# motoko_azure_dragon.net
KiCad netlist of a schematic drawn in EAGLE
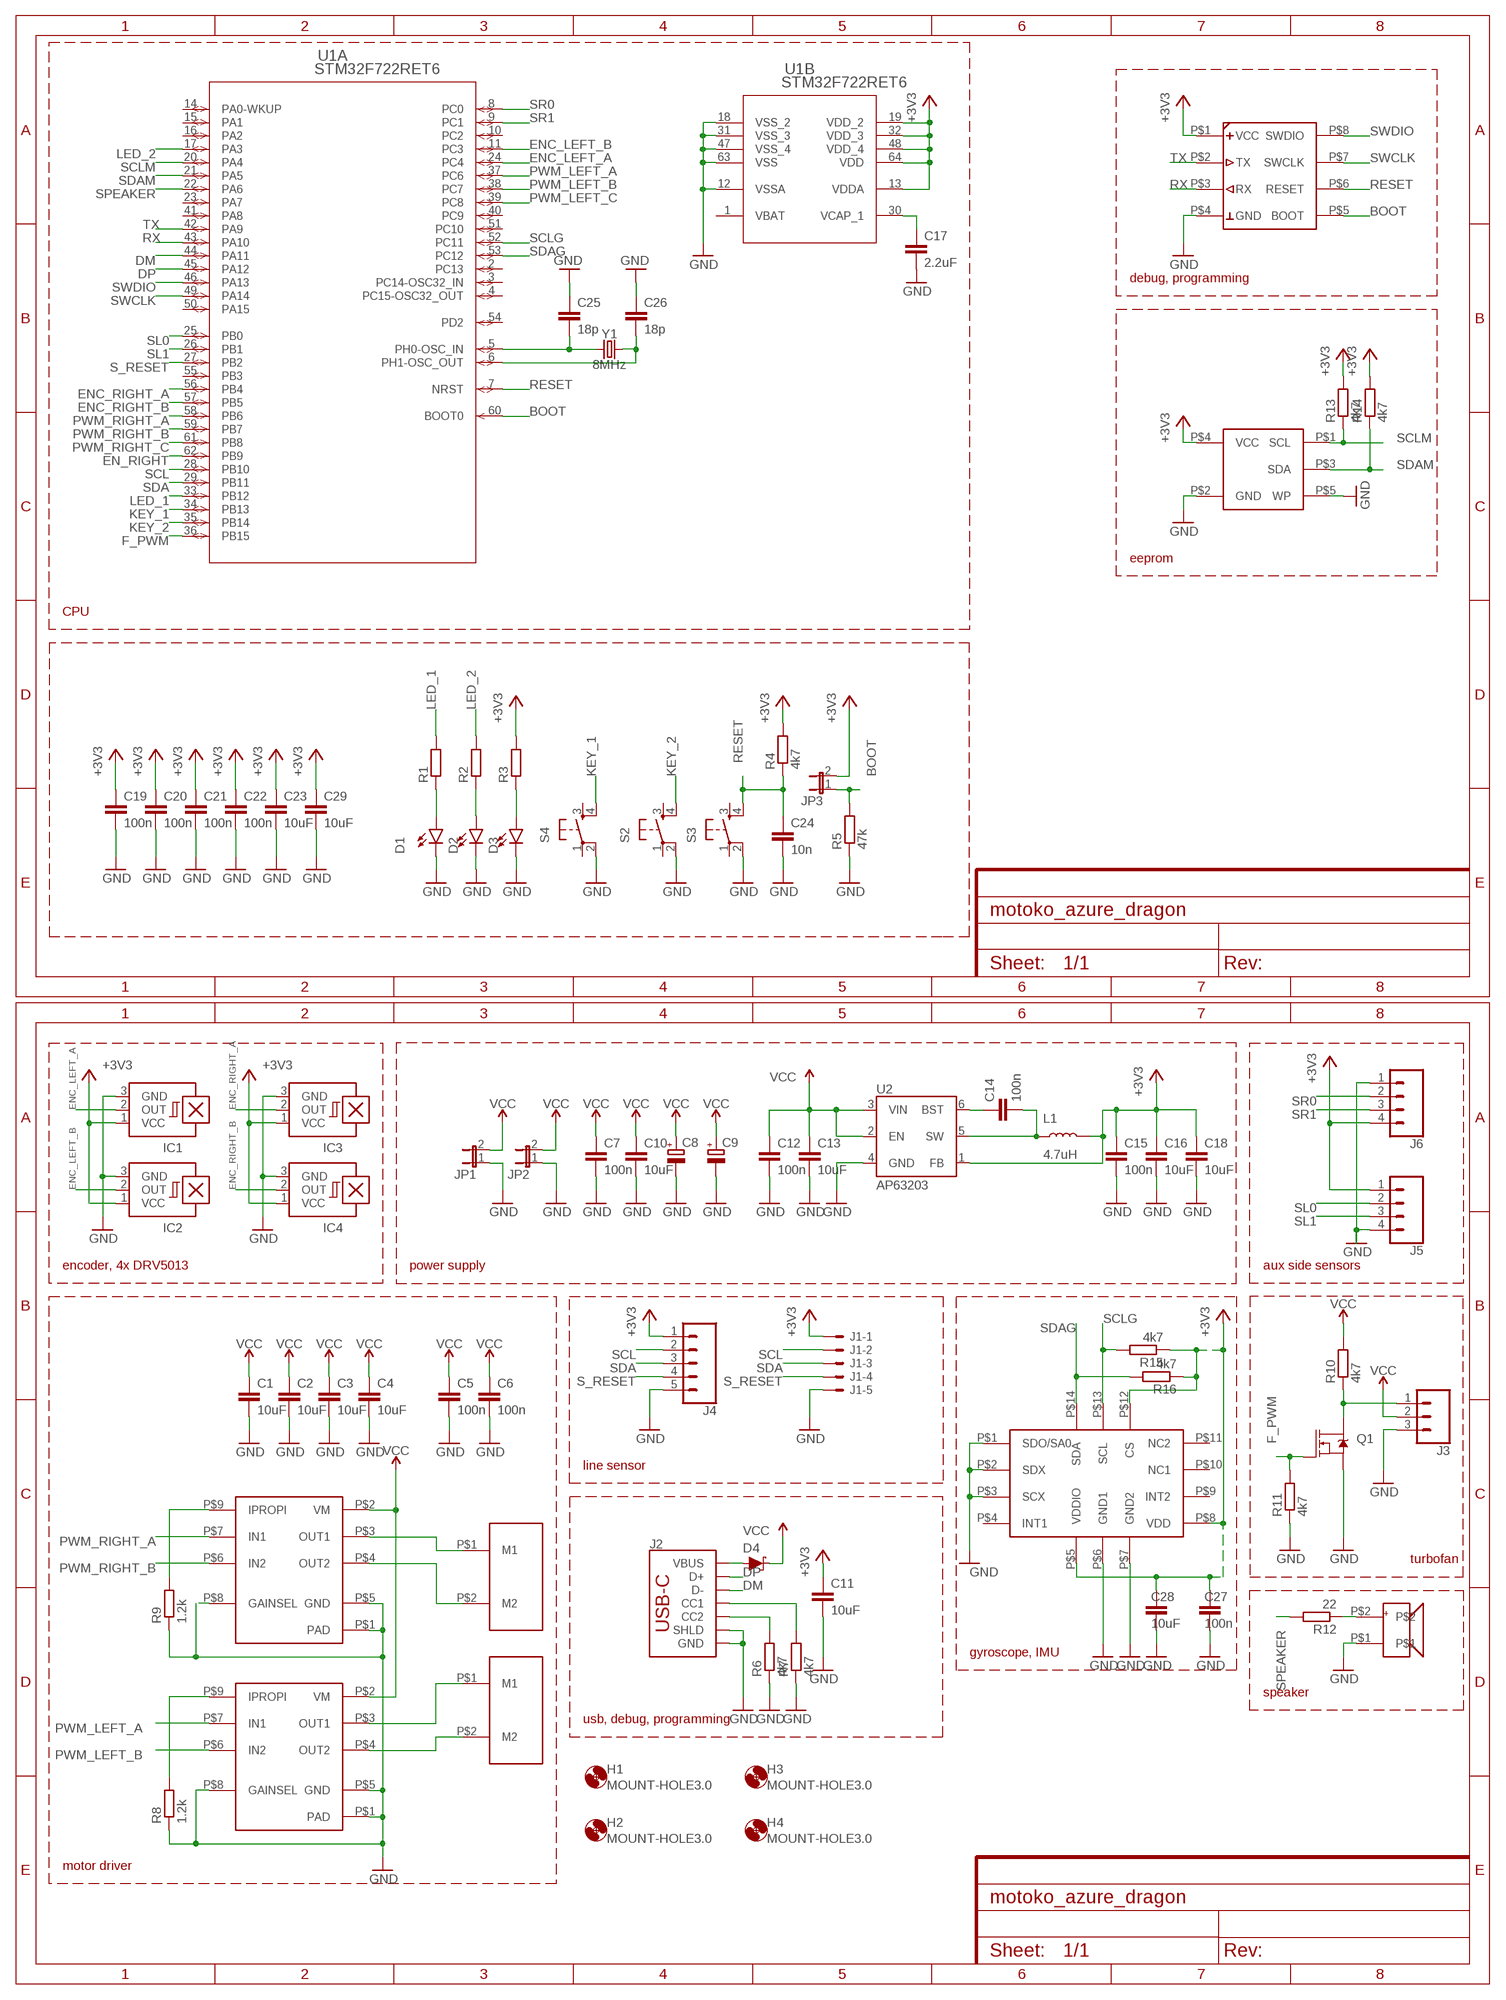
[diagram p0: schematic, sheet 1]

(export (version "E")
  (design (tool "Eeschema 10.0.6"))
  (components
    (comp (ref "C1")
      (value "10uF")
      (footprint "eagle-import:C0805")
      (libsource (lib "eagle-import") (part "C-EUC0805"))
    )
    (comp (ref "C2")
      (value "10uF")
      (footprint "eagle-import:C0805")
      (libsource (lib "eagle-import") (part "C-EUC0805"))
    )
    (comp (ref "C3")
      (value "10uF")
      (footprint "eagle-import:C0805")
      (libsource (lib "eagle-import") (part "C-EUC0805"))
    )
    (comp (ref "C4")
      (value "10uF")
      (footprint "eagle-import:C0805")
      (libsource (lib "eagle-import") (part "C-EUC0805"))
    )
    (comp (ref "C5")
      (value "100n")
      (footprint "eagle-import:C0805")
      (libsource (lib "eagle-import") (part "C-EUC0805"))
    )
    (comp (ref "C6")
      (value "100n")
      (footprint "eagle-import:C0805")
      (libsource (lib "eagle-import") (part "C-EUC0805"))
    )
    (comp (ref "C7")
      (value "100n")
      (footprint "eagle-import:C0805")
      (libsource (lib "eagle-import") (part "C-EUC0805"))
    )
    (comp (ref "C8")
      (value "CPOL-EUB/3528-21W")
      (footprint "eagle-import:B_3528-21W")
      (libsource (lib "eagle-import") (part "CPOL-EUB/3528-21W"))
    )
    (comp (ref "C9")
      (value "CPOL-EUB/3528-21W")
      (footprint "eagle-import:B_3528-21W")
      (libsource (lib "eagle-import") (part "CPOL-EUB/3528-21W"))
    )
    (comp (ref "C10")
      (value "10uF")
      (footprint "eagle-import:C0805")
      (libsource (lib "eagle-import") (part "C-EUC0805"))
    )
    (comp (ref "C11")
      (value "10uF")
      (footprint "eagle-import:C0805")
      (libsource (lib "eagle-import") (part "C-EUC0805"))
    )
    (comp (ref "C12")
      (value "100n")
      (footprint "eagle-import:C0805")
      (libsource (lib "eagle-import") (part "C-EUC0805"))
    )
    (comp (ref "C13")
      (value "10uF")
      (footprint "eagle-import:C0805")
      (libsource (lib "eagle-import") (part "C-EUC0805"))
    )
    (comp (ref "C14")
      (value "100n")
      (footprint "eagle-import:C0805")
      (libsource (lib "eagle-import") (part "C-EUC0805"))
    )
    (comp (ref "C15")
      (value "100n")
      (footprint "eagle-import:C0805")
      (libsource (lib "eagle-import") (part "C-EUC0805"))
    )
    (comp (ref "C16")
      (value "10uF")
      (footprint "eagle-import:C0805")
      (libsource (lib "eagle-import") (part "C-EUC0805"))
    )
    (comp (ref "C17")
      (value "2.2uF")
      (footprint "eagle-import:C0805")
      (libsource (lib "eagle-import") (part "C-EUC0805"))
    )
    (comp (ref "C18")
      (value "10uF")
      (footprint "eagle-import:C0805")
      (libsource (lib "eagle-import") (part "C-EUC0805"))
    )
    (comp (ref "C19")
      (value "100n")
      (footprint "eagle-import:C0805")
      (libsource (lib "eagle-import") (part "C-EUC0805"))
    )
    (comp (ref "C20")
      (value "100n")
      (footprint "eagle-import:C0805")
      (libsource (lib "eagle-import") (part "C-EUC0805"))
    )
    (comp (ref "C21")
      (value "100n")
      (footprint "eagle-import:C0805")
      (libsource (lib "eagle-import") (part "C-EUC0805"))
    )
    (comp (ref "C22")
      (value "100n")
      (footprint "eagle-import:C0805")
      (libsource (lib "eagle-import") (part "C-EUC0805"))
    )
    (comp (ref "C23")
      (value "10uF")
      (footprint "eagle-import:C0805")
      (libsource (lib "eagle-import") (part "C-EUC0805"))
    )
    (comp (ref "C24")
      (value "10n")
      (footprint "eagle-import:C0805")
      (libsource (lib "eagle-import") (part "C-EUC0805"))
    )
    (comp (ref "C25")
      (value "18p")
      (footprint "eagle-import:C0805")
      (libsource (lib "eagle-import") (part "C-EUC0805"))
    )
    (comp (ref "C26")
      (value "18p")
      (footprint "eagle-import:C0805")
      (libsource (lib "eagle-import") (part "C-EUC0805"))
    )
    (comp (ref "C27")
      (value "100n")
      (footprint "eagle-import:C0805")
      (libsource (lib "eagle-import") (part "C-EUC0805"))
    )
    (comp (ref "C28")
      (value "10uF")
      (footprint "eagle-import:C0805")
      (libsource (lib "eagle-import") (part "C-EUC0805"))
    )
    (comp (ref "C29")
      (value "10uF")
      (footprint "eagle-import:C0805")
      (libsource (lib "eagle-import") (part "C-EUC0805"))
    )
    (comp (ref "D1")
      (value "LED1206")
      (footprint "eagle-import:LED-1206")
      (libsource (lib "eagle-import") (part "LED1206"))
    )
    (comp (ref "D2")
      (value "LED1206")
      (footprint "eagle-import:LED-1206")
      (libsource (lib "eagle-import") (part "LED1206"))
    )
    (comp (ref "D3")
      (value "LED1206")
      (footprint "eagle-import:LED-1206")
      (libsource (lib "eagle-import") (part "LED1206"))
    )
    (comp (ref "D4")
      (value "3A/10V/280mV")
      (footprint "eagle-import:SOD-323")
      (libsource (lib "eagle-import") (part "DIODE-SCHOTTKY-BAT60A"))
    )
    (comp (ref "H1")
      (value "MOUNT-HOLE3.0")
      (footprint "eagle-import:3,0")
      (libsource (lib "eagle-import") (part "MOUNT-HOLE3.0"))
    )
    (comp (ref "H2")
      (value "MOUNT-HOLE3.0")
      (footprint "eagle-import:3,0")
      (libsource (lib "eagle-import") (part "MOUNT-HOLE3.0"))
    )
    (comp (ref "H3")
      (value "MOUNT-HOLE3.0")
      (footprint "eagle-import:3,0")
      (libsource (lib "eagle-import") (part "MOUNT-HOLE3.0"))
    )
    (comp (ref "H4")
      (value "MOUNT-HOLE3.0")
      (footprint "eagle-import:3,0")
      (libsource (lib "eagle-import") (part "MOUNT-HOLE3.0"))
    )
    (comp (ref "IC1")
      (value "A1202LH")
      (footprint "eagle-import:SOT23-W")
      (libsource (lib "eagle-import") (part "A12?LH02"))
    )
    (comp (ref "IC2")
      (value "A1202LH")
      (footprint "eagle-import:SOT23-W")
      (libsource (lib "eagle-import") (part "A12?LH02"))
    )
    (comp (ref "IC3")
      (value "A1202LH")
      (footprint "eagle-import:SOT23-W")
      (libsource (lib "eagle-import") (part "A12?LH02"))
    )
    (comp (ref "IC4")
      (value "A1202LH")
      (footprint "eagle-import:SOT23-W")
      (libsource (lib "eagle-import") (part "A12?LH02"))
    )
    (comp (ref "J1")
      (value "XF2L-0535-1")
      (footprint "eagle-import:XF2L-0535-1")
      (fields (field (name "MPN") "XF2L-0535-1A"))
      (libsource (lib "eagle-import") (part "XF2-05?35-1L"))
    )
    (comp (ref "J2")
      (value "USB_C_2-LAYER_PADS")
      (footprint "eagle-import:USB-C-16P-2LAYER-PADS")
      (libsource (lib "eagle-import") (part "USB_C_2-LAYER_PADS"))
    )
    (comp (ref "J3")
      (value "CONN_03LONGPADS")
      (footprint "eagle-import:1X03_LONGPADS")
      (libsource (lib "eagle-import") (part "CONN_03LONGPADS"))
    )
    (comp (ref "J4")
      (value "CONN_051.27MM")
      (footprint "eagle-import:1X05_1.27MM")
      (libsource (lib "eagle-import") (part "CONN_051.27MM"))
    )
    (comp (ref "J5")
      (value "1X04_SMD_STRAIGHT_COMBO")
      (footprint "eagle-import:1X04_SMD_VERTICAL_COMBO")
      (libsource (lib "eagle-import") (part "CONN_04SMD_STRAIGHT_COMBO"))
    )
    (comp (ref "J6")
      (value "1X04_SMD_STRAIGHT_COMBO")
      (footprint "eagle-import:1X04_SMD_VERTICAL_COMBO")
      (libsource (lib "eagle-import") (part "CONN_04SMD_STRAIGHT_COMBO"))
    )
    (comp (ref "JP1")
      (value "JP1E")
      (footprint "eagle-import:JP1")
      (libsource (lib "eagle-import") (part "JP1E"))
    )
    (comp (ref "JP2")
      (value "JP1E")
      (footprint "eagle-import:JP1")
      (libsource (lib "eagle-import") (part "JP1E"))
    )
    (comp (ref "JP3")
      (value "JP1E")
      (footprint "eagle-import:JP1")
      (libsource (lib "eagle-import") (part "JP1E"))
    )
    (comp (ref "L1")
      (value "4.7uH")
      (footprint "eagle-import:CR54")
      (libsource (lib "eagle-import") (part "INDUCTOR-CR54-3.3UH"))
    )
    (comp (ref "Q1")
      (value "5.8A/30V/35mΩ")
      (footprint "eagle-import:SOT23-3")
      (libsource (lib "eagle-import") (part "MOSFET-NCH-AO3404A"))
    )
    (comp (ref "R1")
      (value "R-EU_M0805")
      (footprint "eagle-import:M0805")
      (libsource (lib "eagle-import") (part "R-EU_M0805"))
    )
    (comp (ref "R2")
      (value "R-EU_M0805")
      (footprint "eagle-import:M0805")
      (libsource (lib "eagle-import") (part "R-EU_M0805"))
    )
    (comp (ref "R3")
      (value "R-EU_M0805")
      (footprint "eagle-import:M0805")
      (libsource (lib "eagle-import") (part "R-EU_M0805"))
    )
    (comp (ref "R4")
      (value "4k7")
      (footprint "eagle-import:M0805")
      (libsource (lib "eagle-import") (part "R-EU_M0805"))
    )
    (comp (ref "R5")
      (value "47k")
      (footprint "eagle-import:M0805")
      (libsource (lib "eagle-import") (part "R-EU_M0805"))
    )
    (comp (ref "R6")
      (value "4k7")
      (footprint "eagle-import:M0805")
      (libsource (lib "eagle-import") (part "R-EU_M0805"))
    )
    (comp (ref "R7")
      (value "4k7")
      (footprint "eagle-import:M0805")
      (libsource (lib "eagle-import") (part "R-EU_M0805"))
    )
    (comp (ref "R8")
      (value "1.2k")
      (footprint "eagle-import:M0805")
      (libsource (lib "eagle-import") (part "R-EU_M0805"))
    )
    (comp (ref "R9")
      (value "1.2k")
      (footprint "eagle-import:M0805")
      (libsource (lib "eagle-import") (part "R-EU_M0805"))
    )
    (comp (ref "R10")
      (value "4k7")
      (footprint "eagle-import:M0805")
      (libsource (lib "eagle-import") (part "R-EU_M0805"))
    )
    (comp (ref "R11")
      (value "4k7")
      (footprint "eagle-import:M0805")
      (libsource (lib "eagle-import") (part "R-EU_M0805"))
    )
    (comp (ref "R12")
      (value "22")
      (footprint "eagle-import:M0805")
      (libsource (lib "eagle-import") (part "R-EU_M0805"))
    )
    (comp (ref "R13")
      (value "4k7")
      (footprint "eagle-import:M0805")
      (libsource (lib "eagle-import") (part "R-EU_M0805"))
    )
    (comp (ref "R14")
      (value "4k7")
      (footprint "eagle-import:M0805")
      (libsource (lib "eagle-import") (part "R-EU_M0805"))
    )
    (comp (ref "R15")
      (value "4k7")
      (footprint "eagle-import:M0805")
      (libsource (lib "eagle-import") (part "R-EU_M0805"))
    )
    (comp (ref "R16")
      (value "4k7")
      (footprint "eagle-import:M0805")
      (libsource (lib "eagle-import") (part "R-EU_M0805"))
    )
    (comp (ref "S2")
      (value "TAC_SWITCHSMD")
      (footprint "eagle-import:TACTILE-SWITCH-SMD")
      (libsource (lib "eagle-import") (part "TAC_SWITCHSMD"))
    )
    (comp (ref "S3")
      (value "TAC_SWITCHSMD")
      (footprint "eagle-import:TACTILE-SWITCH-SMD")
      (libsource (lib "eagle-import") (part "TAC_SWITCHSMD"))
    )
    (comp (ref "S4")
      (value "TAC_SWITCHSMD")
      (footprint "eagle-import:TACTILE-SWITCH-SMD")
      (libsource (lib "eagle-import") (part "TAC_SWITCHSMD"))
    )
    (comp (ref "U$2")
      (value "POLOLU_MICRO_METAL_GEAR_MOTOR")
      (footprint "eagle-import:POLOLU_MICRO_METAL_GEAR_MOTOR")
      (libsource (lib "eagle-import") (part "POLOLU_MICRO_METAL_GEAR_MOTOR"))
    )
    (comp (ref "U$3")
      (value "POLOLU_MICRO_METAL_GEAR_MOTOR")
      (footprint "eagle-import:POLOLU_MICRO_METAL_GEAR_MOTOR")
      (libsource (lib "eagle-import") (part "POLOLU_MICRO_METAL_GEAR_MOTOR"))
    )
    (comp (ref "U$4")
      (value "DRV8213")
      (footprint "eagle-import:DSG8")
      (libsource (lib "eagle-import") (part "DRV8213"))
    )
    (comp (ref "U$5")
      (value "DRV8213")
      (footprint "eagle-import:DSG8")
      (libsource (lib "eagle-import") (part "DRV8213"))
    )
    (comp (ref "U$6")
      (value "24LC24_SOT23")
      (footprint "eagle-import:SOT23")
      (libsource (lib "eagle-import") (part "24LC24_SOT23"))
    )
    (comp (ref "U$7")
      (value "DEBUG_CON")
      (footprint "eagle-import:HEADER_4X2_1.27")
      (libsource (lib "eagle-import") (part "DEBUG_CON"))
    )
    (comp (ref "U$8")
      (value "LSM6DSM")
      (footprint "eagle-import:LGA14L")
      (libsource (lib "eagle-import") (part "LSM6DSM"))
    )
    (comp (ref "U$9")
      (value "SPEAKER_SMD_SMT0440")
      (footprint "eagle-import:SPEAKER_SMD_SMT0440")
      (libsource (lib "eagle-import") (part "SPEAKER_SMD_SMT0440"))
    )
    (comp (ref "U1")
      (value "STM32F722RET6")
      (footprint "eagle-import:LQFP64-10X10MM")
      (fields (field (name "COPYRIGHT") "Copyright (C) 2024 Ultra Librarian. All rights reserved."))
      (libsource (lib "eagle-import") (part "STM32F722RET6"))
    )
    (comp (ref "U2")
      (value "AP63203")
      (footprint "eagle-import:SOT23-6")
      (libsource (lib "eagle-import") (part "AP63203"))
    )
    (comp (ref "Y1")
      (value "8MHz")
      (footprint "eagle-import:CRYSTAL-SMD-3.2X2.5MM")
      (libsource (lib "eagle-import") (part "CRYSTALSMD-3.2X2.5"))
    )
  )
  (nets
    (net (code "1") (name "+3V3") (class "Default")
      (node (ref "C11") (pin "1") (pinfunction "1_1") (pintype "passive"))
      (node (ref "C15") (pin "1") (pinfunction "1_1") (pintype "passive"))
      (node (ref "C16") (pin "1") (pinfunction "1_1") (pintype "passive"))
      (node (ref "C18") (pin "1") (pinfunction "1_1") (pintype "passive"))
      (node (ref "C19") (pin "1") (pinfunction "1_1") (pintype "passive"))
      (node (ref "C20") (pin "1") (pinfunction "1_1") (pintype "passive"))
      (node (ref "C21") (pin "1") (pinfunction "1_1") (pintype "passive"))
      (node (ref "C22") (pin "1") (pinfunction "1_1") (pintype "passive"))
      (node (ref "C23") (pin "1") (pinfunction "1_1") (pintype "passive"))
      (node (ref "C27") (pin "1") (pinfunction "1_1") (pintype "passive"))
      (node (ref "C28") (pin "1") (pinfunction "1_1") (pintype "passive"))
      (node (ref "C29") (pin "1") (pinfunction "1_1") (pintype "passive"))
      (node (ref "IC1") (pin "1") (pinfunction "VCC_1") (pintype "power_in"))
      (node (ref "IC2") (pin "1") (pinfunction "VCC_1") (pintype "power_in"))
      (node (ref "IC3") (pin "1") (pinfunction "VCC_1") (pintype "power_in"))
      (node (ref "IC4") (pin "1") (pinfunction "VCC_1") (pintype "power_in"))
      (node (ref "J1") (pin "1") (pinfunction "MSV_1") (pintype "passive"))
      (node (ref "J4") (pin "1") (pinfunction "1_1") (pintype "passive"))
      (node (ref "J5") (pin "1") (pinfunction "1_1") (pintype "passive"))
      (node (ref "J6") (pin "4") (pinfunction "4_4") (pintype "passive"))
      (node (ref "JP3") (pin "2") (pinfunction "2_2") (pintype "passive"))
      (node (ref "L1") (pin "P$2") (pinfunction "2_P$2") (pintype "passive"))
      (node (ref "R13") (pin "2") (pinfunction "2_2") (pintype "passive"))
      (node (ref "R14") (pin "2") (pinfunction "2_2") (pintype "passive"))
      (node (ref "R15") (pin "1") (pinfunction "1_1") (pintype "passive"))
      (node (ref "R16") (pin "1") (pinfunction "1_1") (pintype "passive"))
      (node (ref "R3") (pin "2") (pinfunction "2_2") (pintype "passive"))
      (node (ref "R4") (pin "2") (pinfunction "2_2") (pintype "passive"))
      (node (ref "U$6") (pin "P$4") (pinfunction "VCC_P$4") (pintype "bidirectional"))
      (node (ref "U$7") (pin "P$1") (pinfunction "VCC_P$1") (pintype "bidirectional"))
      (node (ref "U$8") (pin "P$12") (pinfunction "CS_P$12") (pintype "bidirectional"))
      (node (ref "U$8") (pin "P$5") (pinfunction "VDDIO_P$5") (pintype "bidirectional"))
      (node (ref "U$8") (pin "P$8") (pinfunction "VDD_P$8") (pintype "bidirectional"))
      (node (ref "U1") (pin "13") (pinfunction "VDDA_13") (pintype "power_in"))
      (node (ref "U1") (pin "19") (pinfunction "VDD_2_19") (pintype "power_in"))
      (node (ref "U1") (pin "32") (pinfunction "VDD_3_32") (pintype "power_in"))
      (node (ref "U1") (pin "48") (pinfunction "VDD_4_48") (pintype "power_in"))
      (node (ref "U1") (pin "64") (pinfunction "VDD_64") (pintype "power_in"))
      (node (ref "U2") (pin "1") (pinfunction "FB_1") (pintype "bidirectional"))
    )
    (net (code "2") (name "/BOOT") (class "Default")
      (node (ref "JP3") (pin "1") (pinfunction "1_1") (pintype "passive"))
      (node (ref "R5") (pin "2") (pinfunction "2_2") (pintype "passive"))
      (node (ref "U$7") (pin "P$5") (pinfunction "BOOT_P$5") (pintype "bidirectional"))
      (node (ref "U1") (pin "60") (pinfunction "BOOT0_60") (pintype "input"))
    )
    (net (code "3") (name "/DM") (class "Default")
      (node (ref "J2") (pin "A7") (pinfunction "D-_A7") (pintype "bidirectional"))
      (node (ref "J2") (pin "B7") (pinfunction "D-_B7") (pintype "bidirectional"))
      (node (ref "U1") (pin "44") (pinfunction "PA11_44") (pintype "bidirectional"))
    )
    (net (code "4") (name "/DP") (class "Default")
      (node (ref "J2") (pin "A6") (pinfunction "D+_A6") (pintype "bidirectional"))
      (node (ref "J2") (pin "B6") (pinfunction "D+_B6") (pintype "bidirectional"))
      (node (ref "U1") (pin "45") (pinfunction "PA12_45") (pintype "bidirectional"))
    )
    (net (code "5") (name "/ENC_LEFT_A") (class "Default")
      (node (ref "IC1") (pin "2") (pinfunction "OUT_2") (pintype "output"))
      (node (ref "U1") (pin "24") (pinfunction "PC4_24") (pintype "bidirectional"))
    )
    (net (code "6") (name "/ENC_LEFT_B") (class "Default")
      (node (ref "IC2") (pin "2") (pinfunction "OUT_2") (pintype "output"))
      (node (ref "U1") (pin "11") (pinfunction "PC3_11") (pintype "bidirectional"))
    )
    (net (code "7") (name "/ENC_RIGHT_A") (class "Default")
      (node (ref "IC3") (pin "2") (pinfunction "OUT_2") (pintype "output"))
      (node (ref "U1") (pin "56") (pinfunction "PB4_56") (pintype "bidirectional"))
    )
    (net (code "8") (name "/ENC_RIGHT_B") (class "Default")
      (node (ref "IC4") (pin "2") (pinfunction "OUT_2") (pintype "output"))
      (node (ref "U1") (pin "57") (pinfunction "PB5_57") (pintype "bidirectional"))
    )
    (net (code "9") (name "/EN_RIGHT") (class "Default")
      (node (ref "U1") (pin "62") (pinfunction "PB9_62") (pintype "bidirectional"))
    )
    (net (code "10") (name "/F_PWM") (class "Default")
      (node (ref "Q1") (pin "1") (pinfunction "G_1") (pintype "bidirectional"))
      (node (ref "R11") (pin "2") (pinfunction "2_2") (pintype "passive"))
      (node (ref "U1") (pin "36") (pinfunction "PB15_36") (pintype "bidirectional"))
    )
    (net (code "11") (name "/KEY_1") (class "Default")
      (node (ref "S4") (pin "4") (pinfunction "4_4") (pintype "passive"))
      (node (ref "U1") (pin "34") (pinfunction "PB13_34") (pintype "bidirectional"))
    )
    (net (code "12") (name "/KEY_2") (class "Default")
      (node (ref "S2") (pin "4") (pinfunction "4_4") (pintype "passive"))
      (node (ref "U1") (pin "35") (pinfunction "PB14_35") (pintype "bidirectional"))
    )
    (net (code "13") (name "/LED_1") (class "Default")
      (node (ref "R1") (pin "2") (pinfunction "2_2") (pintype "passive"))
      (node (ref "U1") (pin "33") (pinfunction "PB12_33") (pintype "bidirectional"))
    )
    (net (code "14") (name "/LED_2") (class "Default")
      (node (ref "R2") (pin "2") (pinfunction "2_2") (pintype "passive"))
      (node (ref "U1") (pin "17") (pinfunction "PA3_17") (pintype "bidirectional"))
    )
    (net (code "15") (name "/PWM_LEFT_A") (class "Default")
      (node (ref "U$5") (pin "P$7") (pinfunction "IN1_P$7") (pintype "bidirectional"))
      (node (ref "U1") (pin "37") (pinfunction "PC6_37") (pintype "bidirectional"))
    )
    (net (code "16") (name "/PWM_LEFT_B") (class "Default")
      (node (ref "U$5") (pin "P$6") (pinfunction "IN2_P$6") (pintype "bidirectional"))
      (node (ref "U1") (pin "38") (pinfunction "PC7_38") (pintype "bidirectional"))
    )
    (net (code "17") (name "/PWM_LEFT_C") (class "Default")
      (node (ref "U1") (pin "39") (pinfunction "PC8_39") (pintype "bidirectional"))
    )
    (net (code "18") (name "/PWM_RIGHT_A") (class "Default")
      (node (ref "U$4") (pin "P$7") (pinfunction "IN1_P$7") (pintype "bidirectional"))
      (node (ref "U1") (pin "58") (pinfunction "PB6_58") (pintype "bidirectional"))
    )
    (net (code "19") (name "/PWM_RIGHT_B") (class "Default")
      (node (ref "U$4") (pin "P$6") (pinfunction "IN2_P$6") (pintype "bidirectional"))
      (node (ref "U1") (pin "59") (pinfunction "PB7_59") (pintype "bidirectional"))
    )
    (net (code "20") (name "/PWM_RIGHT_C") (class "Default")
      (node (ref "U1") (pin "61") (pinfunction "PB8_61") (pintype "bidirectional"))
    )
    (net (code "21") (name "/RESET") (class "Default")
      (node (ref "C24") (pin "1") (pinfunction "1_1") (pintype "passive"))
      (node (ref "R4") (pin "1") (pinfunction "1_1") (pintype "passive"))
      (node (ref "S3") (pin "4") (pinfunction "4_4") (pintype "passive"))
      (node (ref "U$7") (pin "P$6") (pinfunction "RESET_P$6") (pintype "bidirectional"))
      (node (ref "U1") (pin "7") (pinfunction "NRST_7") (pintype "bidirectional"))
    )
    (net (code "22") (name "/RX") (class "Default")
      (node (ref "U$7") (pin "P$3") (pinfunction "RX_P$3") (pintype "bidirectional"))
      (node (ref "U1") (pin "43") (pinfunction "PA10_43") (pintype "bidirectional"))
    )
    (net (code "23") (name "/SCL") (class "Default")
      (node (ref "J1") (pin "2") (pinfunction "MS_2") (pintype "passive"))
      (node (ref "J4") (pin "2") (pinfunction "2_2") (pintype "passive"))
      (node (ref "U1") (pin "28") (pinfunction "PB10_28") (pintype "bidirectional"))
    )
    (net (code "24") (name "/SCLG") (class "Default")
      (node (ref "R15") (pin "2") (pinfunction "2_2") (pintype "passive"))
      (node (ref "U$8") (pin "P$13") (pinfunction "SCL_P$13") (pintype "bidirectional"))
      (node (ref "U1") (pin "52") (pinfunction "PC11_52") (pintype "bidirectional"))
    )
    (net (code "25") (name "/SCLM") (class "Default")
      (node (ref "R13") (pin "1") (pinfunction "1_1") (pintype "passive"))
      (node (ref "U$6") (pin "P$1") (pinfunction "SCL_P$1") (pintype "bidirectional"))
      (node (ref "U1") (pin "20") (pinfunction "PA4_20") (pintype "bidirectional"))
    )
    (net (code "26") (name "/SDA") (class "Default")
      (node (ref "J1") (pin "3") (pinfunction "MS_3") (pintype "passive"))
      (node (ref "J4") (pin "3") (pinfunction "3_3") (pintype "passive"))
      (node (ref "U1") (pin "29") (pinfunction "PB11_29") (pintype "bidirectional"))
    )
    (net (code "27") (name "/SDAG") (class "Default")
      (node (ref "R16") (pin "2") (pinfunction "2_2") (pintype "passive"))
      (node (ref "U$8") (pin "P$14") (pinfunction "SDA_P$14") (pintype "bidirectional"))
      (node (ref "U1") (pin "53") (pinfunction "PC12_53") (pintype "bidirectional"))
    )
    (net (code "28") (name "/SDAM") (class "Default")
      (node (ref "R14") (pin "1") (pinfunction "1_1") (pintype "passive"))
      (node (ref "U$6") (pin "P$3") (pinfunction "SDA_P$3") (pintype "bidirectional"))
      (node (ref "U1") (pin "21") (pinfunction "PA5_21") (pintype "bidirectional"))
    )
    (net (code "29") (name "/SL0") (class "Default")
      (node (ref "J5") (pin "2") (pinfunction "2_2") (pintype "passive"))
      (node (ref "U1") (pin "25") (pinfunction "PB0_25") (pintype "bidirectional"))
    )
    (net (code "30") (name "/SL1") (class "Default")
      (node (ref "J5") (pin "3") (pinfunction "3_3") (pintype "passive"))
      (node (ref "U1") (pin "26") (pinfunction "PB1_26") (pintype "bidirectional"))
    )
    (net (code "31") (name "/SPEAKER") (class "Default")
      (node (ref "R12") (pin "2") (pinfunction "2_2") (pintype "passive"))
      (node (ref "U1") (pin "22") (pinfunction "PA6_22") (pintype "bidirectional"))
    )
    (net (code "32") (name "/SR0") (class "Default")
      (node (ref "J6") (pin "2") (pinfunction "2_2") (pintype "passive"))
      (node (ref "U1") (pin "8") (pinfunction "PC0_8") (pintype "bidirectional"))
    )
    (net (code "33") (name "/SR1") (class "Default")
      (node (ref "J6") (pin "3") (pinfunction "3_3") (pintype "passive"))
      (node (ref "U1") (pin "9") (pinfunction "PC1_9") (pintype "bidirectional"))
    )
    (net (code "34") (name "/SWCLK") (class "Default")
      (node (ref "U$7") (pin "P$7") (pinfunction "SWCLK_P$7") (pintype "bidirectional"))
      (node (ref "U1") (pin "49") (pinfunction "PA14_49") (pintype "bidirectional"))
    )
    (net (code "35") (name "/SWDIO") (class "Default")
      (node (ref "U$7") (pin "P$8") (pinfunction "SWDIO_P$8") (pintype "bidirectional"))
      (node (ref "U1") (pin "46") (pinfunction "PA13_46") (pintype "bidirectional"))
    )
    (net (code "36") (name "/S_RESET") (class "Default")
      (node (ref "J1") (pin "4") (pinfunction "MS_4") (pintype "passive"))
      (node (ref "J4") (pin "4") (pinfunction "4_4") (pintype "passive"))
      (node (ref "U1") (pin "27") (pinfunction "PB2_27") (pintype "bidirectional"))
    )
    (net (code "37") (name "/TX") (class "Default")
      (node (ref "U$7") (pin "P$2") (pinfunction "TX_P$2") (pintype "bidirectional"))
      (node (ref "U1") (pin "42") (pinfunction "PA9_42") (pintype "bidirectional"))
    )
    (net (code "38") (name "/VBAT") (class "Default")
      (node (ref "U1") (pin "1") (pinfunction "VBAT_1") (pintype "power_in"))
    )
    (net (code "39") (name "GND") (class "Default")
      (node (ref "C1") (pin "2") (pinfunction "2_2") (pintype "passive"))
      (node (ref "C10") (pin "2") (pinfunction "2_2") (pintype "passive"))
      (node (ref "C11") (pin "2") (pinfunction "2_2") (pintype "passive"))
      (node (ref "C12") (pin "2") (pinfunction "2_2") (pintype "passive"))
      (node (ref "C13") (pin "2") (pinfunction "2_2") (pintype "passive"))
      (node (ref "C15") (pin "2") (pinfunction "2_2") (pintype "passive"))
      (node (ref "C16") (pin "2") (pinfunction "2_2") (pintype "passive"))
      (node (ref "C17") (pin "2") (pinfunction "2_2") (pintype "passive"))
      (node (ref "C18") (pin "2") (pinfunction "2_2") (pintype "passive"))
      (node (ref "C19") (pin "2") (pinfunction "2_2") (pintype "passive"))
      (node (ref "C2") (pin "2") (pinfunction "2_2") (pintype "passive"))
      (node (ref "C20") (pin "2") (pinfunction "2_2") (pintype "passive"))
      (node (ref "C21") (pin "2") (pinfunction "2_2") (pintype "passive"))
      (node (ref "C22") (pin "2") (pinfunction "2_2") (pintype "passive"))
      (node (ref "C23") (pin "2") (pinfunction "2_2") (pintype "passive"))
      (node (ref "C24") (pin "2") (pinfunction "2_2") (pintype "passive"))
      (node (ref "C25") (pin "1") (pinfunction "1_1") (pintype "passive"))
      (node (ref "C26") (pin "1") (pinfunction "1_1") (pintype "passive"))
      (node (ref "C27") (pin "2") (pinfunction "2_2") (pintype "passive"))
      (node (ref "C28") (pin "2") (pinfunction "2_2") (pintype "passive"))
      (node (ref "C29") (pin "2") (pinfunction "2_2") (pintype "passive"))
      (node (ref "C3") (pin "2") (pinfunction "2_2") (pintype "passive"))
      (node (ref "C4") (pin "2") (pinfunction "2_2") (pintype "passive"))
      (node (ref "C5") (pin "2") (pinfunction "2_2") (pintype "passive"))
      (node (ref "C6") (pin "2") (pinfunction "2_2") (pintype "passive"))
      (node (ref "C7") (pin "2") (pinfunction "2_2") (pintype "passive"))
      (node (ref "C8") (pin "-") (pinfunction "-_-") (pintype "passive"))
      (node (ref "C9") (pin "-") (pinfunction "-_-") (pintype "passive"))
      (node (ref "D1") (pin "C") (pinfunction "C_C") (pintype "passive"))
      (node (ref "D2") (pin "C") (pinfunction "C_C") (pintype "passive"))
      (node (ref "D3") (pin "C") (pinfunction "C_C") (pintype "passive"))
      (node (ref "IC1") (pin "3") (pinfunction "GND_3") (pintype "power_in"))
      (node (ref "IC2") (pin "3") (pinfunction "GND_3") (pintype "power_in"))
      (node (ref "IC3") (pin "3") (pinfunction "GND_3") (pintype "power_in"))
      (node (ref "IC4") (pin "3") (pinfunction "GND_3") (pintype "power_in"))
      (node (ref "J1") (pin "5") (pinfunction "MS_5") (pintype "passive"))
      (node (ref "J2") (pin "GND") (pinfunction "GND_GND") (pintype "bidirectional"))
      (node (ref "J2") (pin "GND2") (pinfunction "GND_GND2") (pintype "bidirectional"))
      (node (ref "J2") (pin "SHLD1") (pinfunction "SHLD_SHLD1") (pintype "bidirectional"))
      (node (ref "J2") (pin "SHLD2") (pinfunction "SHLD_SHLD2") (pintype "bidirectional"))
      (node (ref "J2") (pin "SHLD3") (pinfunction "SHLD_SHLD3") (pintype "bidirectional"))
      (node (ref "J2") (pin "SHLD4") (pinfunction "SHLD_SHLD4") (pintype "bidirectional"))
      (node (ref "J3") (pin "3") (pinfunction "3_3") (pintype "passive"))
      (node (ref "J4") (pin "5") (pinfunction "5_5") (pintype "passive"))
      (node (ref "J5") (pin "4") (pinfunction "4_4") (pintype "passive"))
      (node (ref "J6") (pin "1") (pinfunction "1_1") (pintype "passive"))
      (node (ref "JP1") (pin "1") (pinfunction "1_1") (pintype "passive"))
      (node (ref "JP2") (pin "1") (pinfunction "1_1") (pintype "passive"))
      (node (ref "Q1") (pin "2") (pinfunction "S_2") (pintype "bidirectional"))
      (node (ref "R11") (pin "1") (pinfunction "1_1") (pintype "passive"))
      (node (ref "R5") (pin "1") (pinfunction "1_1") (pintype "passive"))
      (node (ref "R6") (pin "1") (pinfunction "1_1") (pintype "passive"))
      (node (ref "R7") (pin "1") (pinfunction "1_1") (pintype "passive"))
      (node (ref "R8") (pin "1") (pinfunction "1_1") (pintype "passive"))
      (node (ref "R9") (pin "1") (pinfunction "1_1") (pintype "passive"))
      (node (ref "S2") (pin "2") (pinfunction "2_2") (pintype "passive"))
      (node (ref "S3") (pin "2") (pinfunction "2_2") (pintype "passive"))
      (node (ref "S4") (pin "2") (pinfunction "2_2") (pintype "passive"))
      (node (ref "U$4") (pin "P$1") (pinfunction "PAD_P$1") (pintype "bidirectional"))
      (node (ref "U$4") (pin "P$5") (pinfunction "GND_P$5") (pintype "bidirectional"))
      (node (ref "U$4") (pin "P$8") (pinfunction "GAINSEL_P$8") (pintype "bidirectional"))
      (node (ref "U$5") (pin "P$1") (pinfunction "PAD_P$1") (pintype "bidirectional"))
      (node (ref "U$5") (pin "P$5") (pinfunction "GND_P$5") (pintype "bidirectional"))
      (node (ref "U$5") (pin "P$8") (pinfunction "GAINSEL_P$8") (pintype "bidirectional"))
      (node (ref "U$6") (pin "P$2") (pinfunction "GND_P$2") (pintype "bidirectional"))
      (node (ref "U$6") (pin "P$5") (pinfunction "WP_P$5") (pintype "bidirectional"))
      (node (ref "U$7") (pin "P$4") (pinfunction "GND_P$4") (pintype "bidirectional"))
      (node (ref "U$8") (pin "P$1") (pinfunction "SDO/SA0_P$1") (pintype "bidirectional"))
      (node (ref "U$8") (pin "P$2") (pinfunction "SDX_P$2") (pintype "bidirectional"))
      (node (ref "U$8") (pin "P$3") (pinfunction "SCX_P$3") (pintype "bidirectional"))
      (node (ref "U$8") (pin "P$6") (pinfunction "GND1_P$6") (pintype "bidirectional"))
      (node (ref "U$8") (pin "P$7") (pinfunction "GND2_P$7") (pintype "bidirectional"))
      (node (ref "U$9") (pin "P$1") (pinfunction "P$1_P$1") (pintype "bidirectional"))
      (node (ref "U1") (pin "12") (pinfunction "VSSA_12") (pintype "power_in"))
      (node (ref "U1") (pin "18") (pinfunction "VSS_2_18") (pintype "power_in"))
      (node (ref "U1") (pin "31") (pinfunction "VSS_3_31") (pintype "power_in"))
      (node (ref "U1") (pin "47") (pinfunction "VSS_4_47") (pintype "power_in"))
      (node (ref "U1") (pin "63") (pinfunction "VSS_63") (pintype "power_in"))
      (node (ref "U2") (pin "4") (pinfunction "GND_4") (pintype "bidirectional"))
    )
    (net (code "40") (name "Net-(D1-PadA)") (class "Default")
      (node (ref "D1") (pin "A") (pinfunction "A_A") (pintype "passive"))
      (node (ref "R1") (pin "1") (pinfunction "1_1") (pintype "passive"))
    )
    (net (code "41") (name "Net-(D2-PadA)") (class "Default")
      (node (ref "D2") (pin "A") (pinfunction "A_A") (pintype "passive"))
      (node (ref "R2") (pin "1") (pinfunction "1_1") (pintype "passive"))
    )
    (net (code "42") (name "Net-(D3-PadA)") (class "Default")
      (node (ref "D3") (pin "A") (pinfunction "A_A") (pintype "passive"))
      (node (ref "R3") (pin "1") (pinfunction "1_1") (pintype "passive"))
    )
    (net (code "43") (name "Net-(D4-PadA)") (class "Default")
      (node (ref "D4") (pin "A") (pinfunction "A_A") (pintype "passive"))
      (node (ref "J2") (pin "VBUS1") (pinfunction "VBUS_VBUS1") (pintype "bidirectional"))
      (node (ref "J2") (pin "VBUS2") (pinfunction "VBUS_VBUS2") (pintype "bidirectional"))
    )
    (net (code "44") (name "Net-(J2-CC1)") (class "Default")
      (node (ref "J2") (pin "A5") (pinfunction "CC1_A5") (pintype "bidirectional"))
      (node (ref "R7") (pin "2") (pinfunction "2_2") (pintype "passive"))
    )
    (net (code "45") (name "Net-(J2-CC2)") (class "Default")
      (node (ref "J2") (pin "B5") (pinfunction "CC2_B5") (pintype "bidirectional"))
      (node (ref "R6") (pin "2") (pinfunction "2_2") (pintype "passive"))
    )
    (net (code "46") (name "Net-(L1-1)") (class "Default")
      (node (ref "C14") (pin "2") (pinfunction "2_2") (pintype "passive"))
      (node (ref "L1") (pin "P$1") (pinfunction "1_P$1") (pintype "passive"))
      (node (ref "U2") (pin "5") (pinfunction "SW_5") (pintype "bidirectional"))
    )
    (net (code "47") (name "Net-(Q1-D)") (class "Default")
      (node (ref "J3") (pin "1") (pinfunction "1_1") (pintype "passive"))
      (node (ref "Q1") (pin "3") (pinfunction "D_3") (pintype "bidirectional"))
      (node (ref "R10") (pin "1") (pinfunction "1_1") (pintype "passive"))
    )
    (net (code "48") (name "Net-(R12-Pad1)") (class "Default")
      (node (ref "R12") (pin "1") (pinfunction "1_1") (pintype "passive"))
      (node (ref "U$9") (pin "P$2") (pinfunction "P$2_P$2") (pintype "bidirectional"))
    )
    (net (code "49") (name "Net-(U$2-M1)") (class "Default")
      (node (ref "U$2") (pin "P$1") (pinfunction "M1_P$1") (pintype "bidirectional"))
      (node (ref "U$4") (pin "P$3") (pinfunction "OUT1_P$3") (pintype "bidirectional"))
    )
    (net (code "50") (name "Net-(U$2-M2)") (class "Default")
      (node (ref "U$2") (pin "P$2") (pinfunction "M2_P$2") (pintype "bidirectional"))
      (node (ref "U$4") (pin "P$4") (pinfunction "OUT2_P$4") (pintype "bidirectional"))
    )
    (net (code "51") (name "Net-(U$3-M1)") (class "Default")
      (node (ref "U$3") (pin "P$1") (pinfunction "M1_P$1") (pintype "bidirectional"))
      (node (ref "U$5") (pin "P$3") (pinfunction "OUT1_P$3") (pintype "bidirectional"))
    )
    (net (code "52") (name "Net-(U$3-M2)") (class "Default")
      (node (ref "U$3") (pin "P$2") (pinfunction "M2_P$2") (pintype "bidirectional"))
      (node (ref "U$5") (pin "P$4") (pinfunction "OUT2_P$4") (pintype "bidirectional"))
    )
    (net (code "53") (name "Net-(U$4-IPROPI)") (class "Default")
      (node (ref "R9") (pin "2") (pinfunction "2_2") (pintype "passive"))
      (node (ref "U$4") (pin "P$9") (pinfunction "IPROPI_P$9") (pintype "bidirectional"))
    )
    (net (code "54") (name "Net-(U$5-IPROPI)") (class "Default")
      (node (ref "R8") (pin "2") (pinfunction "2_2") (pintype "passive"))
      (node (ref "U$5") (pin "P$9") (pinfunction "IPROPI_P$9") (pintype "bidirectional"))
    )
    (net (code "55") (name "Net-(U1A-PH0-OSC_IN)") (class "Default")
      (node (ref "C25") (pin "2") (pinfunction "2_2") (pintype "passive"))
      (node (ref "U1") (pin "5") (pinfunction "PH0-OSC_IN_5") (pintype "bidirectional"))
      (node (ref "Y1") (pin "1") (pinfunction "1_1") (pintype "passive"))
    )
    (net (code "56") (name "Net-(U1A-PH1-OSC_OUT)") (class "Default")
      (node (ref "C26") (pin "2") (pinfunction "2_2") (pintype "passive"))
      (node (ref "U1") (pin "6") (pinfunction "PH1-OSC_OUT_6") (pintype "bidirectional"))
      (node (ref "Y1") (pin "3") (pinfunction "2_3") (pintype "passive"))
    )
    (net (code "57") (name "Net-(U1B-VCAP_1)") (class "Default")
      (node (ref "C17") (pin "1") (pinfunction "1_1") (pintype "passive"))
      (node (ref "U1") (pin "30") (pinfunction "VCAP_1_30") (pintype "power_in"))
    )
    (net (code "58") (name "Net-(U2-BST)") (class "Default")
      (node (ref "C14") (pin "1") (pinfunction "1_1") (pintype "passive"))
      (node (ref "U2") (pin "6") (pinfunction "BST_6") (pintype "bidirectional"))
    )
    (net (code "59") (name "VCC") (class "Default")
      (node (ref "C1") (pin "1") (pinfunction "1_1") (pintype "passive"))
      (node (ref "C10") (pin "1") (pinfunction "1_1") (pintype "passive"))
      (node (ref "C12") (pin "1") (pinfunction "1_1") (pintype "passive"))
      (node (ref "C13") (pin "1") (pinfunction "1_1") (pintype "passive"))
      (node (ref "C2") (pin "1") (pinfunction "1_1") (pintype "passive"))
      (node (ref "C3") (pin "1") (pinfunction "1_1") (pintype "passive"))
      (node (ref "C4") (pin "1") (pinfunction "1_1") (pintype "passive"))
      (node (ref "C5") (pin "1") (pinfunction "1_1") (pintype "passive"))
      (node (ref "C6") (pin "1") (pinfunction "1_1") (pintype "passive"))
      (node (ref "C7") (pin "1") (pinfunction "1_1") (pintype "passive"))
      (node (ref "C8") (pin "+") (pinfunction "+_+") (pintype "passive"))
      (node (ref "C9") (pin "+") (pinfunction "+_+") (pintype "passive"))
      (node (ref "D4") (pin "C") (pinfunction "C_C") (pintype "passive"))
      (node (ref "J3") (pin "2") (pinfunction "2_2") (pintype "passive"))
      (node (ref "JP1") (pin "2") (pinfunction "2_2") (pintype "passive"))
      (node (ref "JP2") (pin "2") (pinfunction "2_2") (pintype "passive"))
      (node (ref "R10") (pin "2") (pinfunction "2_2") (pintype "passive"))
      (node (ref "U$4") (pin "P$2") (pinfunction "VM_P$2") (pintype "bidirectional"))
      (node (ref "U$5") (pin "P$2") (pinfunction "VM_P$2") (pintype "bidirectional"))
      (node (ref "U2") (pin "2") (pinfunction "EN_2") (pintype "bidirectional"))
      (node (ref "U2") (pin "3") (pinfunction "VIN_3") (pintype "bidirectional"))
    )
    (net (code "60") (name "unconnected-(S2-Pad1)") (class "Default")
      (node (ref "S2") (pin "1") (pinfunction "1_1") (pintype "passive"))
    )
    (net (code "61") (name "unconnected-(S2-Pad3)") (class "Default")
      (node (ref "S2") (pin "3") (pinfunction "3_3") (pintype "passive"))
    )
    (net (code "62") (name "unconnected-(S3-Pad1)") (class "Default")
      (node (ref "S3") (pin "1") (pinfunction "1_1") (pintype "passive"))
    )
    (net (code "63") (name "unconnected-(S3-Pad3)") (class "Default")
      (node (ref "S3") (pin "3") (pinfunction "3_3") (pintype "passive"))
    )
    (net (code "64") (name "unconnected-(S4-Pad1)") (class "Default")
      (node (ref "S4") (pin "1") (pinfunction "1_1") (pintype "passive"))
    )
    (net (code "65") (name "unconnected-(S4-Pad3)") (class "Default")
      (node (ref "S4") (pin "3") (pinfunction "3_3") (pintype "passive"))
    )
    (net (code "66") (name "unconnected-(U$8-INT1-PadP$4)") (class "Default")
      (node (ref "U$8") (pin "P$4") (pinfunction "INT1_P$4") (pintype "bidirectional"))
    )
    (net (code "67") (name "unconnected-(U$8-INT2-PadP$9)") (class "Default")
      (node (ref "U$8") (pin "P$9") (pinfunction "INT2_P$9") (pintype "bidirectional"))
    )
    (net (code "68") (name "unconnected-(U$8-NC1-PadP$10)") (class "Default")
      (node (ref "U$8") (pin "P$10") (pinfunction "NC1_P$10") (pintype "bidirectional"))
    )
    (net (code "69") (name "unconnected-(U$8-NC2-PadP$11)") (class "Default")
      (node (ref "U$8") (pin "P$11") (pinfunction "NC2_P$11") (pintype "bidirectional"))
    )
    (net (code "70") (name "unconnected-(U1A-PA0-WKUP-Pad14)") (class "Default")
      (node (ref "U1") (pin "14") (pinfunction "PA0-WKUP_14") (pintype "bidirectional"))
    )
    (net (code "71") (name "unconnected-(U1A-PA1-Pad15)") (class "Default")
      (node (ref "U1") (pin "15") (pinfunction "PA1_15") (pintype "bidirectional"))
    )
    (net (code "72") (name "unconnected-(U1A-PA2-Pad16)") (class "Default")
      (node (ref "U1") (pin "16") (pinfunction "PA2_16") (pintype "bidirectional"))
    )
    (net (code "73") (name "unconnected-(U1A-PA7-Pad23)") (class "Default")
      (node (ref "U1") (pin "23") (pinfunction "PA7_23") (pintype "bidirectional"))
    )
    (net (code "74") (name "unconnected-(U1A-PA8-Pad41)") (class "Default")
      (node (ref "U1") (pin "41") (pinfunction "PA8_41") (pintype "bidirectional"))
    )
    (net (code "75") (name "unconnected-(U1A-PA15-Pad50)") (class "Default")
      (node (ref "U1") (pin "50") (pinfunction "PA15_50") (pintype "bidirectional"))
    )
    (net (code "76") (name "unconnected-(U1A-PB3-Pad55)") (class "Default")
      (node (ref "U1") (pin "55") (pinfunction "PB3_55") (pintype "bidirectional"))
    )
    (net (code "77") (name "unconnected-(U1A-PC2-Pad10)") (class "Default")
      (node (ref "U1") (pin "10") (pinfunction "PC2_10") (pintype "bidirectional"))
    )
    (net (code "78") (name "unconnected-(U1A-PC9-Pad40)") (class "Default")
      (node (ref "U1") (pin "40") (pinfunction "PC9_40") (pintype "bidirectional"))
    )
    (net (code "79") (name "unconnected-(U1A-PC10-Pad51)") (class "Default")
      (node (ref "U1") (pin "51") (pinfunction "PC10_51") (pintype "bidirectional"))
    )
    (net (code "80") (name "unconnected-(U1A-PC13-Pad2)") (class "Default")
      (node (ref "U1") (pin "2") (pinfunction "PC13_2") (pintype "bidirectional"))
    )
    (net (code "81") (name "unconnected-(U1A-PC14-OSC32_IN-Pad3)") (class "Default")
      (node (ref "U1") (pin "3") (pinfunction "PC14-OSC32_IN_3") (pintype "bidirectional"))
    )
    (net (code "82") (name "unconnected-(U1A-PC15-OSC32_OUT-Pad4)") (class "Default")
      (node (ref "U1") (pin "4") (pinfunction "PC15-OSC32_OUT_4") (pintype "bidirectional"))
    )
    (net (code "83") (name "unconnected-(U1A-PD2-Pad54)") (class "Default")
      (node (ref "U1") (pin "54") (pinfunction "PD2_54") (pintype "bidirectional"))
    )
  )
)
